# Sensor_Sch.net
KiCad netlist of a schematic drawn in Altium Designer
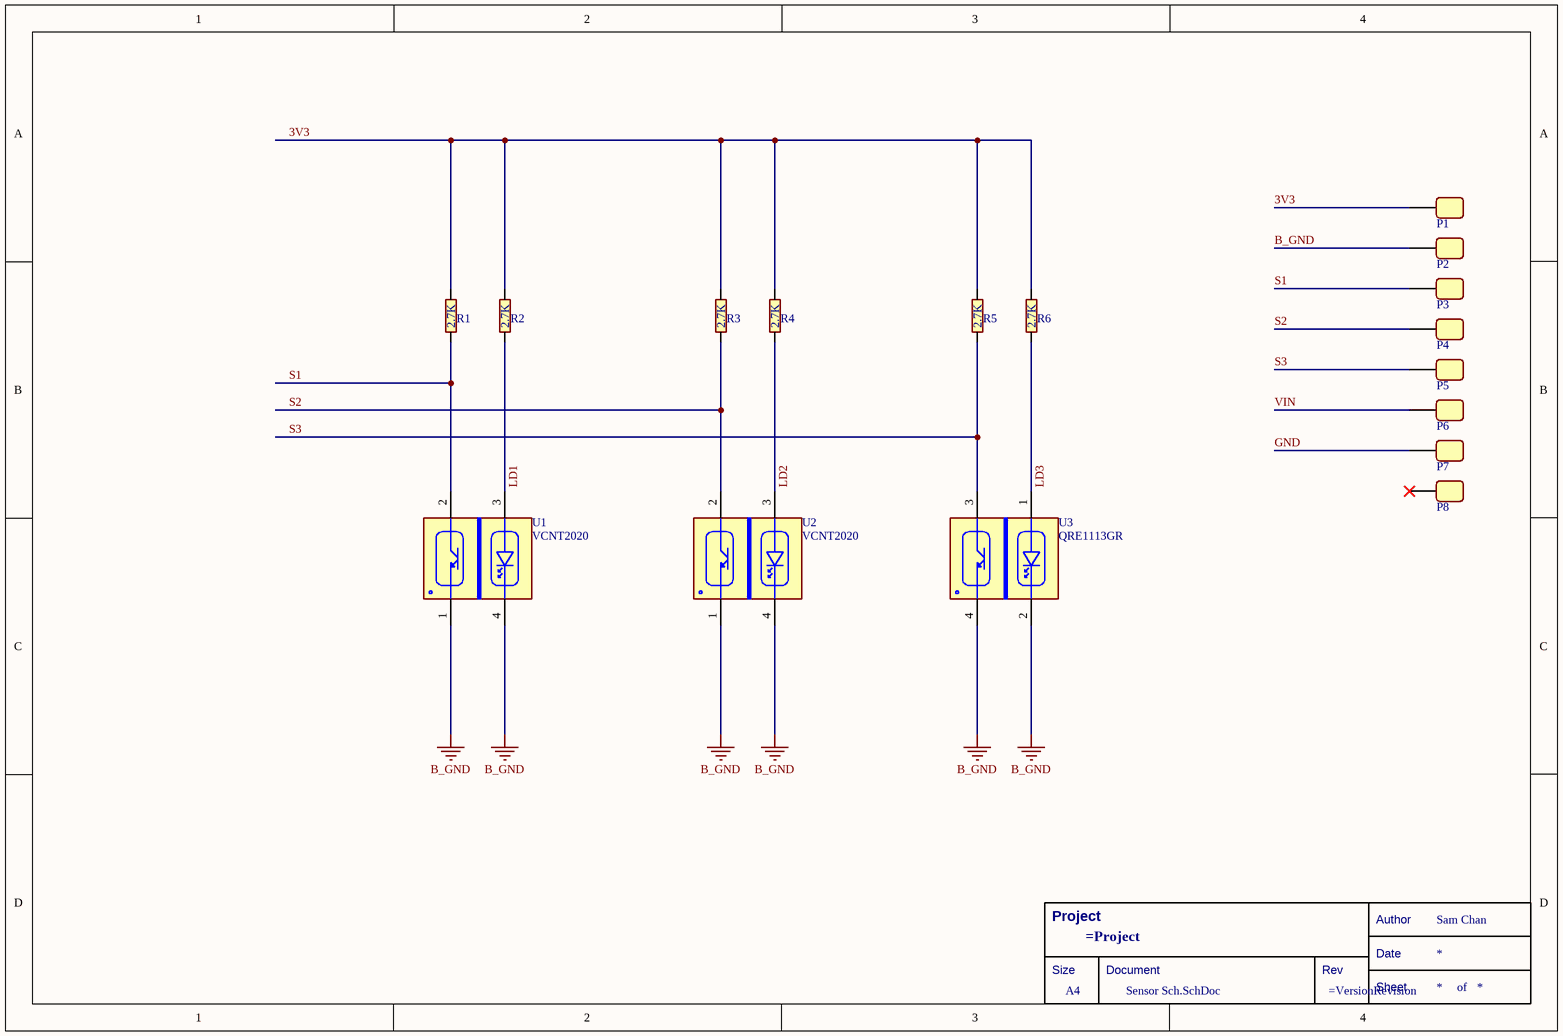
[diagram p0: Sensor Sch.SchDoc]

(export (version "E")
  (design (tool "Eeschema 10.0.6"))
  (components
    (comp (ref "*")
      (value "Title Block")
      (description "Standard Title Block")
      (libsource (lib "Cube Library") (part "Title Block"))
    )
    (comp (ref "P1")
      (value "PAD_4")
      (footprint "PAD_0.5X1MM")
      (description "a Rec pad, 0.5X1mm")
      (libsource (lib "Cube Library") (part "PAD_4"))
    )
    (comp (ref "P2")
      (value "PAD_4")
      (footprint "PAD_0.5X1MM")
      (description "a Rec pad, 0.5X1mm")
      (libsource (lib "Cube Library") (part "PAD_4"))
    )
    (comp (ref "P3")
      (value "PAD_4")
      (footprint "PAD_0.5X1MM")
      (description "a Rec pad, 0.5X1mm")
      (libsource (lib "Cube Library") (part "PAD_4"))
    )
    (comp (ref "P4")
      (value "PAD_4")
      (footprint "PAD_0.5X1MM")
      (description "a Rec pad, 0.5X1mm")
      (libsource (lib "Cube Library") (part "PAD_4"))
    )
    (comp (ref "P5")
      (value "PAD_4")
      (footprint "PAD_0.5X1MM")
      (description "a Rec pad, 0.5X1mm")
      (libsource (lib "Cube Library") (part "PAD_4"))
    )
    (comp (ref "P6")
      (value "PAD_4")
      (footprint "PAD_0.5X1MM")
      (description "a Rec pad, 0.5X1mm")
      (libsource (lib "Cube Library") (part "PAD_4"))
    )
    (comp (ref "P7")
      (value "PAD_4")
      (footprint "PAD_0.5X1MM")
      (description "a Rec pad, 0.5X1mm")
      (libsource (lib "Cube Library") (part "PAD_4"))
    )
    (comp (ref "P8")
      (value "PAD_4")
      (footprint "PAD_0.5X1MM")
      (description "a Rec pad, 0.5X1mm")
      (libsource (lib "Cube Library") (part "PAD_4"))
    )
    (comp (ref "R1")
      (value "2.7K")
      (footprint "RESC0402X04N")
      (description "RES SMD 2.7K OHM 1% 1/16W 0402")
      (fields
        (field (name "MANUFACTURER") "YAGEO")
        (field (name "MANUFACTURER PART NUMBER") "AC0402FR-072K7L")
        (field (name "RESISTANCE") "2.7K")
      )
      (libsource (lib "Cube Library") (part "RES 2.7K"))
    )
    (comp (ref "R2")
      (value "2.7K")
      (footprint "RESC0402X04N")
      (description "RES SMD 2.7K OHM 1% 1/16W 0402")
      (fields
        (field (name "MANUFACTURER") "YAGEO")
        (field (name "MANUFACTURER PART NUMBER") "AC0402FR-072K7L")
        (field (name "RESISTANCE") "2.7K")
      )
      (libsource (lib "Cube Library") (part "RES 2.7K"))
    )
    (comp (ref "R3")
      (value "2.7K")
      (footprint "RESC0402X04N")
      (description "RES SMD 2.7K OHM 1% 1/16W 0402")
      (fields
        (field (name "MANUFACTURER") "YAGEO")
        (field (name "MANUFACTURER PART NUMBER") "AC0402FR-072K7L")
        (field (name "RESISTANCE") "2.7K")
      )
      (libsource (lib "Cube Library") (part "RES 2.7K"))
    )
    (comp (ref "R4")
      (value "2.7K")
      (footprint "RESC0402X04N")
      (description "RES SMD 2.7K OHM 1% 1/16W 0402")
      (fields
        (field (name "MANUFACTURER") "YAGEO")
        (field (name "MANUFACTURER PART NUMBER") "AC0402FR-072K7L")
        (field (name "RESISTANCE") "2.7K")
      )
      (libsource (lib "Cube Library") (part "RES 2.7K"))
    )
    (comp (ref "R5")
      (value "2.7K")
      (footprint "RESC0402X04N")
      (description "RES SMD 2.7K OHM 1% 1/16W 0402")
      (fields
        (field (name "MANUFACTURER") "YAGEO")
        (field (name "MANUFACTURER PART NUMBER") "AC0402FR-072K7L")
        (field (name "RESISTANCE") "2.7K")
      )
      (libsource (lib "Cube Library") (part "RES 2.7K"))
    )
    (comp (ref "R6")
      (value "2.7K")
      (footprint "RESC0402X04N")
      (description "RES SMD 2.7K OHM 1% 1/16W 0402")
      (fields
        (field (name "MANUFACTURER") "YAGEO")
        (field (name "MANUFACTURER PART NUMBER") "AC0402FR-072K7L")
        (field (name "RESISTANCE") "2.7K")
      )
      (libsource (lib "Cube Library") (part "RES 2.7K"))
    )
    (comp (ref "U1")
      (value "VCNT2020")
      (footprint "VCNT2020")
      (description "REFLECTIVE SENSOR WITH PTR OUTPU")
      (fields (field (name "MANUFACTURER") "Vishay Semiconductor Opto Division"))
      (libsource (lib "Cube Library") (part "VCNT2020"))
    )
    (comp (ref "U2")
      (value "VCNT2020")
      (footprint "VCNT2020")
      (description "REFLECTIVE SENSOR WITH PTR OUTPU")
      (fields (field (name "MANUFACTURER") "Vishay Semiconductor Opto Division"))
      (libsource (lib "Cube Library") (part "VCNT2020"))
    )
    (comp (ref "U3")
      (value "QRE1113GR")
      (footprint "QRE1113GR")
      (description "SENSOR OPTO TRANS REFL SMD PHOTO")
      (fields (field (name "MANUFACTURER") "ON Semiconductor"))
      (libsource (lib "Cube Library") (part "QRE1113GR"))
    )
  )
  (nets
    (net (code "1") (name "/3V3") (class "Default")
      (node (ref "P1") (pin "1") (pinfunction "1_1") (pintype "passive"))
      (node (ref "R1") (pin "2") (pinfunction "2_2") (pintype "passive"))
      (node (ref "R2") (pin "2") (pinfunction "2_2") (pintype "passive"))
      (node (ref "R3") (pin "2") (pinfunction "2_2") (pintype "passive"))
      (node (ref "R4") (pin "2") (pinfunction "2_2") (pintype "passive"))
      (node (ref "R5") (pin "2") (pinfunction "2_2") (pintype "passive"))
      (node (ref "R6") (pin "2") (pinfunction "2_2") (pintype "passive"))
    )
    (net (code "2") (name "/GND") (class "Default")
      (node (ref "P7") (pin "1") (pinfunction "1_1") (pintype "passive"))
    )
    (net (code "3") (name "/LD1") (class "Default")
      (node (ref "R2") (pin "1") (pinfunction "1_1") (pintype "passive"))
      (node (ref "U1") (pin "3") (pinfunction "3_3") (pintype "passive"))
    )
    (net (code "4") (name "/LD2") (class "Default")
      (node (ref "R4") (pin "1") (pinfunction "1_1") (pintype "passive"))
      (node (ref "U2") (pin "3") (pinfunction "3_3") (pintype "passive"))
    )
    (net (code "5") (name "/LD3") (class "Default")
      (node (ref "R6") (pin "1") (pinfunction "1_1") (pintype "passive"))
      (node (ref "U3") (pin "1") (pinfunction "1_1") (pintype "passive"))
    )
    (net (code "6") (name "/S1") (class "Default")
      (node (ref "P3") (pin "1") (pinfunction "1_1") (pintype "passive"))
      (node (ref "R1") (pin "1") (pinfunction "1_1") (pintype "passive"))
      (node (ref "U1") (pin "2") (pinfunction "2_2") (pintype "passive"))
    )
    (net (code "7") (name "/S2") (class "Default")
      (node (ref "P4") (pin "1") (pinfunction "1_1") (pintype "passive"))
      (node (ref "R3") (pin "1") (pinfunction "1_1") (pintype "passive"))
      (node (ref "U2") (pin "2") (pinfunction "2_2") (pintype "passive"))
    )
    (net (code "8") (name "/S3") (class "Default")
      (node (ref "P5") (pin "1") (pinfunction "1_1") (pintype "passive"))
      (node (ref "R5") (pin "1") (pinfunction "1_1") (pintype "passive"))
      (node (ref "U3") (pin "3") (pinfunction "3_3") (pintype "passive"))
    )
    (net (code "9") (name "/VIN") (class "Default")
      (node (ref "P6") (pin "1") (pinfunction "1_1") (pintype "passive"))
    )
    (net (code "10") (name "B_GND") (class "Default")
      (node (ref "P2") (pin "1") (pinfunction "1_1") (pintype "passive"))
      (node (ref "U1") (pin "1") (pinfunction "1_1") (pintype "passive"))
      (node (ref "U1") (pin "4") (pinfunction "4_4") (pintype "passive"))
      (node (ref "U2") (pin "1") (pinfunction "1_1") (pintype "passive"))
      (node (ref "U2") (pin "4") (pinfunction "4_4") (pintype "passive"))
      (node (ref "U3") (pin "2") (pinfunction "2_2") (pintype "passive"))
      (node (ref "U3") (pin "4") (pinfunction "4_4") (pintype "passive"))
    )
    (net (code "11") (name "unconnected-(P8-Pad1)") (class "Default")
      (node (ref "P8") (pin "1") (pinfunction "1_1") (pintype "passive+no_connect"))
    )
  )
)
